# JlinkSwitch.net
KiCad netlist of a schematic drawn in Altium Designer
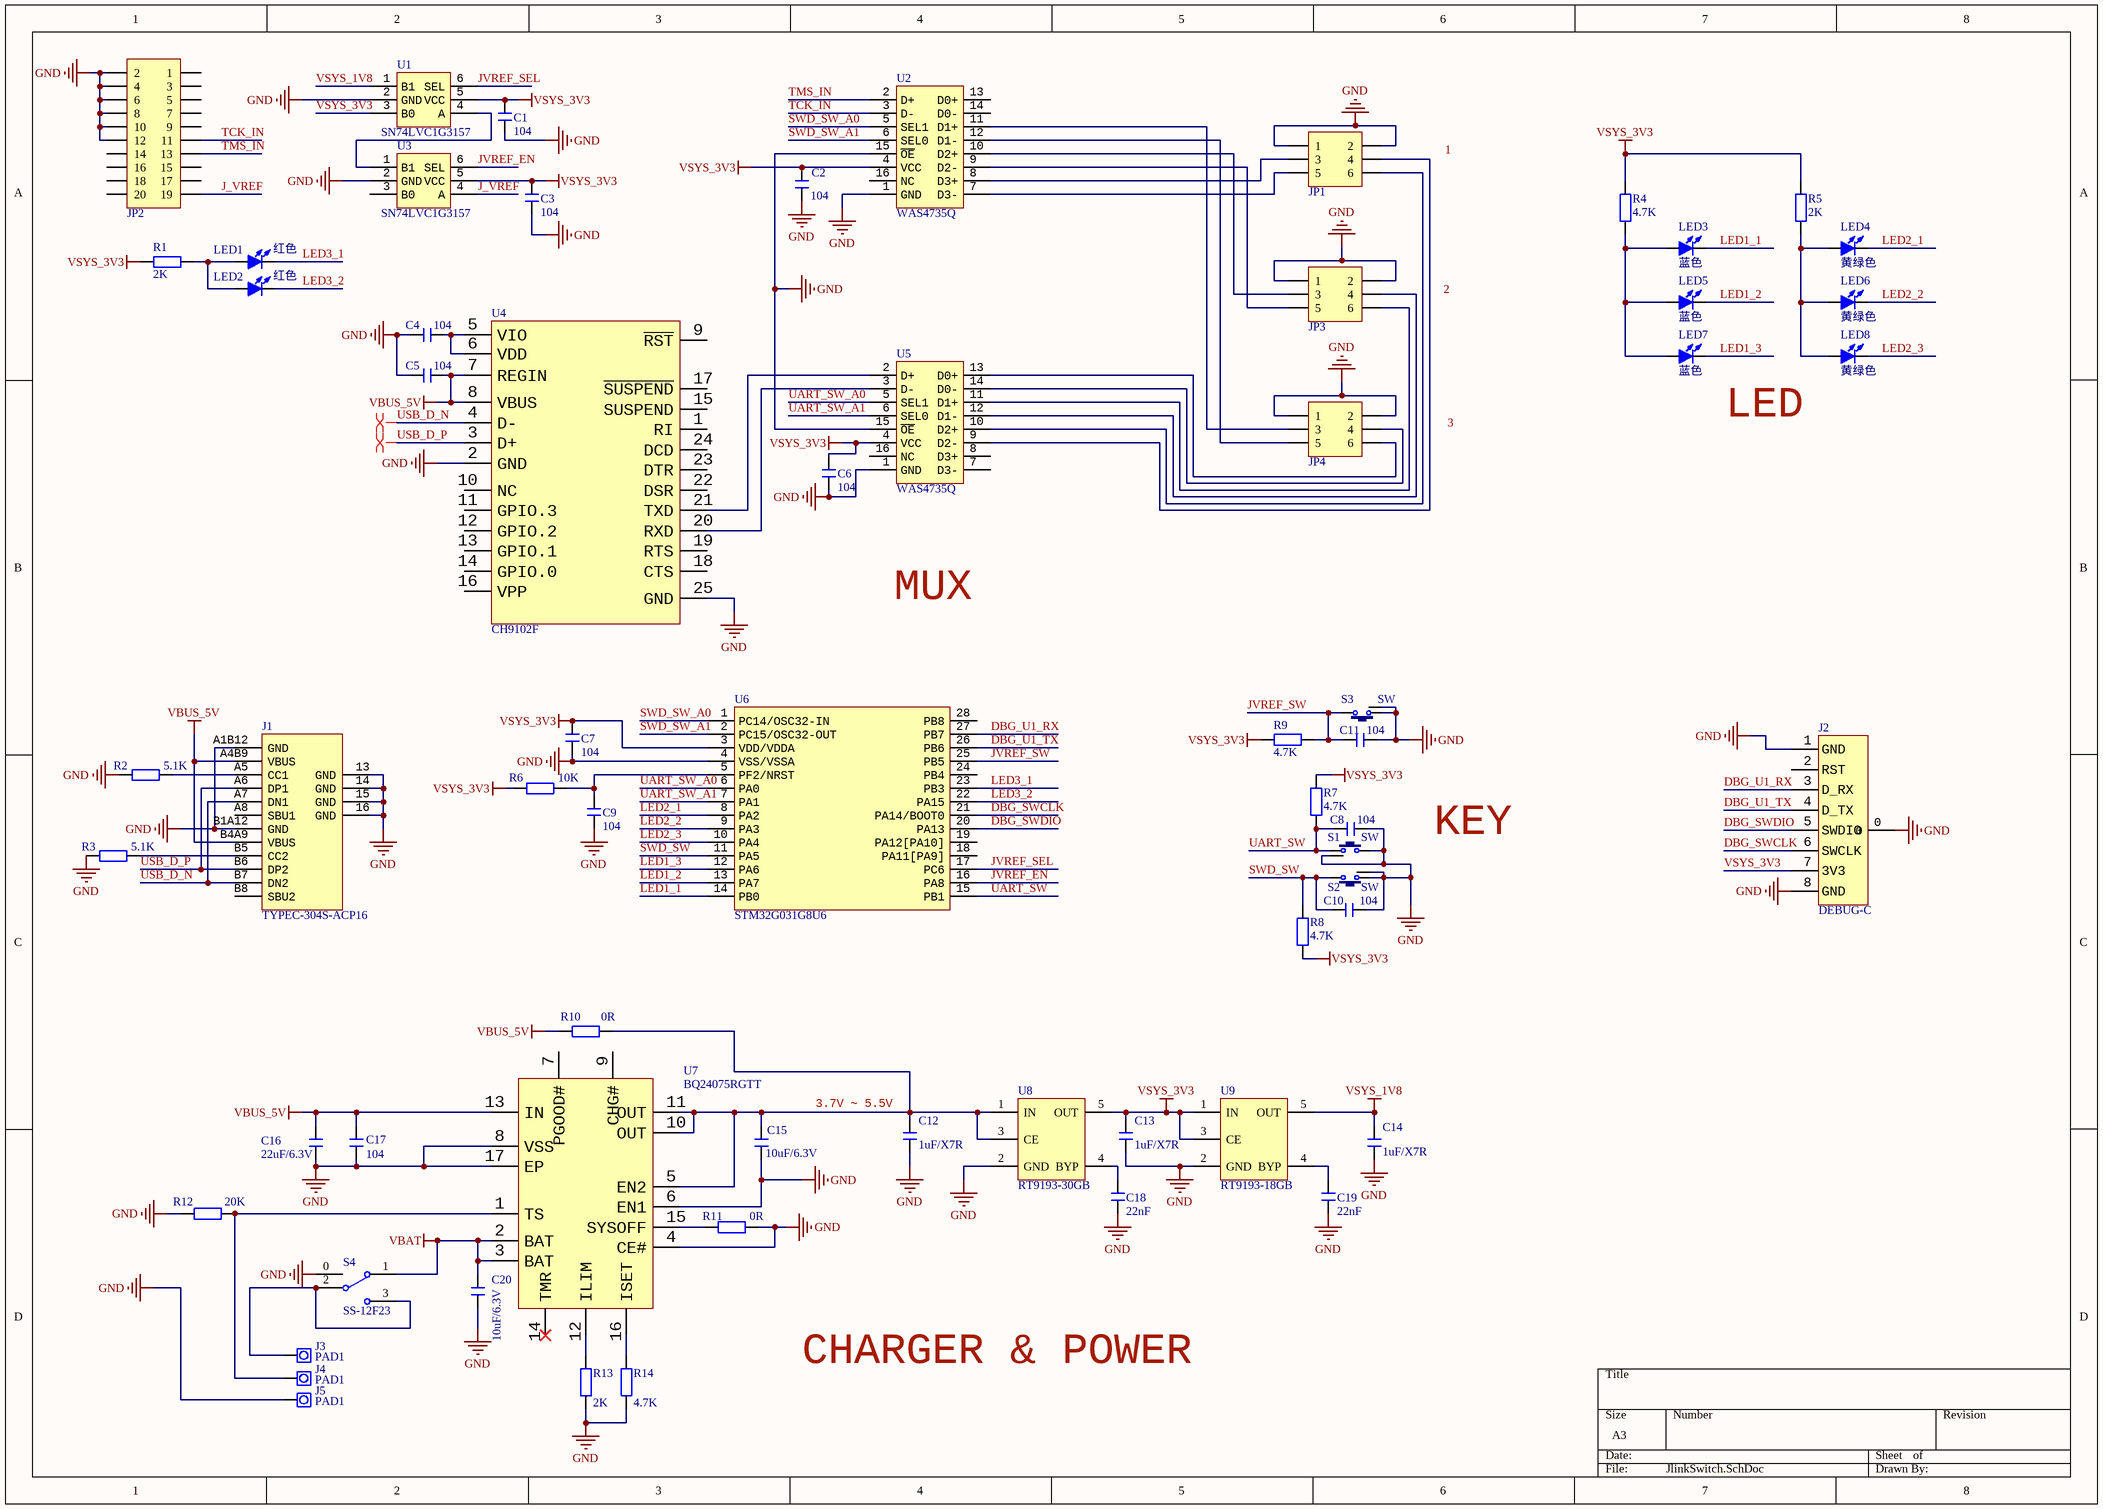
[diagram p0: JlinkSwitch.SchDoc]

(export (version "E")
  (design (tool "Eeschema 10.0.6"))
  (components
    (comp (ref "C1")
      (value "104")
      (footprint "C 0402_L")
      (description "无极性贴片电容")
      (fields (field (name "版权归属") "源创客"))
      (libsource (lib "3.1   - 电阻-电容-电感") (part "C"))
    )
    (comp (ref "C2")
      (value "104")
      (footprint "C 0402_L")
      (description "无极性贴片电容")
      (fields (field (name "版权归属") "源创客"))
      (libsource (lib "3.1   - 电阻-电容-电感") (part "C"))
    )
    (comp (ref "C3")
      (value "104")
      (footprint "C 0402_L")
      (description "无极性贴片电容")
      (fields (field (name "版权归属") "源创客"))
      (libsource (lib "3.1   - 电阻-电容-电感") (part "C"))
    )
    (comp (ref "C4")
      (value "104")
      (footprint "C 0402_L")
      (description "无极性贴片电容")
      (fields (field (name "版权归属") "源创客"))
      (libsource (lib "3.1   - 电阻-电容-电感") (part "C"))
    )
    (comp (ref "C5")
      (value "104")
      (footprint "C 0402_L")
      (description "无极性贴片电容")
      (fields (field (name "版权归属") "源创客"))
      (libsource (lib "3.1   - 电阻-电容-电感") (part "C"))
    )
    (comp (ref "C6")
      (value "104")
      (footprint "C 0402_L")
      (description "无极性贴片电容")
      (fields (field (name "版权归属") "源创客"))
      (libsource (lib "3.1   - 电阻-电容-电感") (part "C"))
    )
    (comp (ref "C7")
      (value "104")
      (footprint "C 0402_L")
      (description "无极性贴片电容")
      (fields (field (name "版权归属") "源创客"))
      (libsource (lib "3.1   - 电阻-电容-电感") (part "C"))
    )
    (comp (ref "C8")
      (value "104")
      (footprint "C 0402_L")
      (description "无极性贴片电容")
      (fields (field (name "版权归属") "源创客"))
      (libsource (lib "3.1   - 电阻-电容-电感") (part "C"))
    )
    (comp (ref "C9")
      (value "104")
      (footprint "C 0402_L")
      (description "无极性贴片电容")
      (fields (field (name "版权归属") "源创客"))
      (libsource (lib "3.1   - 电阻-电容-电感") (part "C"))
    )
    (comp (ref "C10")
      (value "104")
      (footprint "C 0402_L")
      (description "无极性贴片电容")
      (fields (field (name "版权归属") "源创客"))
      (libsource (lib "3.1   - 电阻-电容-电感") (part "C"))
    )
    (comp (ref "C11")
      (value "104")
      (footprint "C 0402_L")
      (description "无极性贴片电容")
      (fields (field (name "版权归属") "源创客"))
      (libsource (lib "3.1   - 电阻-电容-电感") (part "C"))
    )
    (comp (ref "C12")
      (value "1uF/X7R")
      (footprint "C 0402_L")
      (description "无极性贴片电容")
      (fields (field (name "版权归属") "源创客"))
      (libsource (lib "3.1   - 电阻-电容-电感") (part "C"))
    )
    (comp (ref "C13")
      (value "1uF/X7R")
      (footprint "C 0402_L")
      (description "无极性贴片电容")
      (fields (field (name "版权归属") "源创客"))
      (libsource (lib "3.1   - 电阻-电容-电感") (part "C"))
    )
    (comp (ref "C14")
      (value "1uF/X7R")
      (footprint "C 0402_L")
      (description "无极性贴片电容")
      (fields (field (name "版权归属") "源创客"))
      (libsource (lib "3.1   - 电阻-电容-电感") (part "C"))
    )
    (comp (ref "C15")
      (value "10uF/6.3V")
      (footprint "C 0603_L")
      (description "无极性贴片电容")
      (fields (field (name "版权归属") "源创客"))
      (libsource (lib "3.1   - 电阻-电容-电感") (part "C"))
    )
    (comp (ref "C16")
      (value "22uF/6.3V")
      (footprint "C 0603_L")
      (description "无极性贴片电容")
      (fields (field (name "版权归属") "源创客"))
      (libsource (lib "3.1   - 电阻-电容-电感") (part "C"))
    )
    (comp (ref "C17")
      (value "104")
      (footprint "C 0402_L")
      (description "无极性贴片电容")
      (fields (field (name "版权归属") "源创客"))
      (libsource (lib "3.1   - 电阻-电容-电感") (part "C"))
    )
    (comp (ref "C18")
      (value "22nF")
      (footprint "C 0402_L")
      (description "无极性贴片电容")
      (fields (field (name "版权归属") "源创客"))
      (libsource (lib "3.1   - 电阻-电容-电感") (part "C"))
    )
    (comp (ref "C19")
      (value "22nF")
      (footprint "C 0402_L")
      (description "无极性贴片电容")
      (fields (field (name "版权归属") "源创客"))
      (libsource (lib "3.1   - 电阻-电容-电感") (part "C"))
    )
    (comp (ref "C20")
      (value "10uF/6.3V")
      (footprint "C 0603_L")
      (description "无极性贴片电容")
      (fields (field (name "版权归属") "源创客"))
      (libsource (lib "3.1   - 电阻-电容-电感") (part "C"))
    )
    (comp (ref "J1")
      (value "TYPEC-304S-ACP16")
      (footprint "USBC-16P-卧插")
      (description "TYPEC母座16P")
      (libsource (lib "4.1   - 接口类") (part "USB-C/16P"))
    )
    (comp (ref "J2")
      (value "DEBUG-C")
      (footprint "FPC0.5 1H-WS-8P-NARROW")
      (description "带RST的调试接口")
      (libsource (lib "4.1   - 接口类") (part "DEBUG-C"))
    )
    (comp (ref "J3")
      (value "PAD1")
      (footprint "PAD")
      (description "引线焊盘")
      (libsource (lib "15.1 - 未分类器件") (part "PAD1"))
    )
    (comp (ref "J4")
      (value "PAD1")
      (footprint "PAD")
      (description "引线焊盘")
      (libsource (lib "15.1 - 未分类器件") (part "PAD1"))
    )
    (comp (ref "J5")
      (value "PAD1")
      (footprint "PAD")
      (description "引线焊盘")
      (libsource (lib "15.1 - 未分类器件") (part "PAD1"))
    )
    (comp (ref "JP1")
      (value "Header3X2")
      (footprint "HDR2.54-LI-2X3P-侧贴")
      (description "3*2P接插件")
      (fields (field (name "版权归属") "源创客"))
      (libsource (lib "4.5   - 接插件-脚距2.54") (part "Header 3X2"))
    )
    (comp (ref "JP2")
      (value "Header 2X10")
      (footprint "HDR2.54-LI-M-2X10P-侧贴")
      (description "10*2P接插件")
      (fields (field (name "版权归属") "源创客"))
      (libsource (lib "4.5   - 接插件-脚距2.54") (part "Header 10X2"))
    )
    (comp (ref "JP3")
      (value "Header3X2")
      (footprint "HDR2.54-LI-2X3P-侧贴")
      (description "3*2P接插件")
      (fields (field (name "版权归属") "源创客"))
      (libsource (lib "4.5   - 接插件-脚距2.54") (part "Header 3X2"))
    )
    (comp (ref "JP4")
      (value "Header3X2")
      (footprint "HDR2.54-LI-2X3P-侧贴")
      (description "3*2P接插件")
      (fields (field (name "版权归属") "源创客"))
      (libsource (lib "4.5   - 接插件-脚距2.54") (part "Header 3X2"))
    )
    (comp (ref "LED1")
      (value "红色")
      (footprint "LED 0402R")
      (description "贴片LED")
      (fields (field (name "版权归属") "源创客"))
      (libsource (lib "9.1   - LED") (part "LED-SMD"))
    )
    (comp (ref "LED2")
      (value "红色")
      (footprint "LED 0402R")
      (description "贴片LED")
      (fields (field (name "版权归属") "源创客"))
      (libsource (lib "9.1   - LED") (part "LED-SMD"))
    )
    (comp (ref "LED3")
      (value "蓝色")
      (footprint "LED 0402R")
      (description "贴片LED")
      (fields (field (name "版权归属") "源创客"))
      (libsource (lib "9.1   - LED") (part "LED-SMD"))
    )
    (comp (ref "LED4")
      (value "黄绿色")
      (footprint "LED 0402R")
      (description "贴片LED")
      (fields (field (name "版权归属") "源创客"))
      (libsource (lib "9.1   - LED") (part "LED-SMD"))
    )
    (comp (ref "LED5")
      (value "蓝色")
      (footprint "LED 0402R")
      (description "贴片LED")
      (fields (field (name "版权归属") "源创客"))
      (libsource (lib "9.1   - LED") (part "LED-SMD"))
    )
    (comp (ref "LED6")
      (value "黄绿色")
      (footprint "LED 0402R")
      (description "贴片LED")
      (fields (field (name "版权归属") "源创客"))
      (libsource (lib "9.1   - LED") (part "LED-SMD"))
    )
    (comp (ref "LED7")
      (value "蓝色")
      (footprint "LED 0402R")
      (description "贴片LED")
      (fields (field (name "版权归属") "源创客"))
      (libsource (lib "9.1   - LED") (part "LED-SMD"))
    )
    (comp (ref "LED8")
      (value "黄绿色")
      (footprint "LED 0402R")
      (description "贴片LED")
      (fields (field (name "版权归属") "源创客"))
      (libsource (lib "9.1   - LED") (part "LED-SMD"))
    )
    (comp (ref "R1")
      (value "2K")
      (footprint "R 0402_L")
      (description "贴片电阻")
      (fields (field (name "版权归属") "源创客"))
      (libsource (lib "3.1   - 电阻-电容-电感") (part "R"))
    )
    (comp (ref "R2")
      (value "5.1K")
      (footprint "R 0402_L")
      (description "贴片电阻")
      (fields (field (name "版权归属") "源创客"))
      (libsource (lib "3.1   - 电阻-电容-电感") (part "R"))
    )
    (comp (ref "R3")
      (value "5.1K")
      (footprint "R 0402_L")
      (description "贴片电阻")
      (fields (field (name "版权归属") "源创客"))
      (libsource (lib "3.1   - 电阻-电容-电感") (part "R"))
    )
    (comp (ref "R4")
      (value "4.7K")
      (footprint "R 0402_L")
      (description "贴片电阻")
      (fields (field (name "版权归属") "源创客"))
      (libsource (lib "3.1   - 电阻-电容-电感") (part "R"))
    )
    (comp (ref "R5")
      (value "2K")
      (footprint "R 0402_L")
      (description "贴片电阻")
      (fields (field (name "版权归属") "源创客"))
      (libsource (lib "3.1   - 电阻-电容-电感") (part "R"))
    )
    (comp (ref "R6")
      (value "10K")
      (footprint "R 0402_L")
      (description "贴片电阻")
      (fields (field (name "版权归属") "源创客"))
      (libsource (lib "3.1   - 电阻-电容-电感") (part "R"))
    )
    (comp (ref "R7")
      (value "4.7K")
      (footprint "R 0402_L")
      (description "贴片电阻")
      (fields (field (name "版权归属") "源创客"))
      (libsource (lib "3.1   - 电阻-电容-电感") (part "R"))
    )
    (comp (ref "R8")
      (value "4.7K")
      (footprint "R 0402_L")
      (description "贴片电阻")
      (fields (field (name "版权归属") "源创客"))
      (libsource (lib "3.1   - 电阻-电容-电感") (part "R"))
    )
    (comp (ref "R9")
      (value "4.7K")
      (footprint "R 0402_L")
      (description "贴片电阻")
      (fields (field (name "版权归属") "源创客"))
      (libsource (lib "3.1   - 电阻-电容-电感") (part "R"))
    )
    (comp (ref "R10")
      (value "0R")
      (footprint "R 0603_L")
      (description "贴片电阻")
      (fields (field (name "版权归属") "源创客"))
      (libsource (lib "3.1   - 电阻-电容-电感") (part "R"))
    )
    (comp (ref "R11")
      (value "0R")
      (footprint "R 0402_L")
      (description "贴片电阻")
      (fields (field (name "版权归属") "源创客"))
      (libsource (lib "3.1   - 电阻-电容-电感") (part "R"))
    )
    (comp (ref "R12")
      (value "20K")
      (footprint "R 0402_L")
      (description "贴片电阻")
      (fields (field (name "版权归属") "源创客"))
      (libsource (lib "3.1   - 电阻-电容-电感") (part "R"))
    )
    (comp (ref "R13")
      (value "2K")
      (footprint "R 0402_L")
      (description "贴片电阻")
      (fields (field (name "版权归属") "源创客"))
      (libsource (lib "3.1   - 电阻-电容-电感") (part "R"))
    )
    (comp (ref "R14")
      (value "4.7K")
      (footprint "R 0402_L")
      (description "贴片电阻")
      (fields (field (name "版权归属") "源创客"))
      (libsource (lib "3.1   - 电阻-电容-电感") (part "R"))
    )
    (comp (ref "S1")
      (value "SW")
      (footprint "TS 2*4*3.5")
      (description "侧按 按键开关单刀单掷")
      (libsource (lib "") (part "TSW_1"))
    )
    (comp (ref "S2")
      (value "SW")
      (footprint "TS 2*4*3.5")
      (description "侧按 按键开关单刀单掷")
      (libsource (lib "5.1   - 按键-开关") (part "TSW"))
    )
    (comp (ref "S3")
      (value "SW")
      (footprint "TS 2*4*3.5")
      (description "侧按 按键开关单刀单掷")
      (libsource (lib "5.1   - 按键-开关") (part "TSW"))
    )
    (comp (ref "S4")
      (value "SS-12F23")
      (footprint "MSK-12C01-07")
      (description "1路波动开关")
      (fields (field (name "版权归属") "源创客"))
      (libsource (lib "5.1   - 按键-开关") (part "SSW-1P"))
    )
    (comp (ref "U1")
      (value "SN74LVC1G3157")
      (footprint "SC70-6")
      (description "SPDT 7Ω")
      (libsource (lib "1.1   - IC芯片") (part "SN74LVC1G3157DCKR"))
    )
    (comp (ref "U2")
      (value "WAS4735Q")
      (footprint "QFN16-1826")
      (description "模拟开关/多路复用器")
      (libsource (lib "1.1   - IC芯片") (part "WAS4735Q"))
    )
    (comp (ref "U3")
      (value "SN74LVC1G3157")
      (footprint "SC70-6")
      (description "SPDT 7Ω")
      (libsource (lib "1.1   - IC芯片") (part "SN74LVC1G3157DCKR"))
    )
    (comp (ref "U4")
      (value "CH9102F")
      (footprint "QFN24 4x4_L")
      (description "USB转串口芯片")
      (libsource (lib "1.1   - IC芯片") (part "CH9102F"))
    )
    (comp (ref "U5")
      (value "WAS4735Q")
      (footprint "QFN16-1826")
      (description "模拟开关/多路复用器")
      (libsource (lib "1.1   - IC芯片") (part "WAS4735Q"))
    )
    (comp (ref "U6")
      (value "STM32G031G8U6")
      (footprint "UFQFPN-28 4X4")
      (description "M0单片机 QFPN28")
      (libsource (lib "2.1   - STM32系列单片机") (part "STM32G031G8U6"))
    )
    (comp (ref "U7")
      (value "BQ24075RGTT")
      (footprint "VQFN-16-EP(3X3)")
      (description "单节1.5A线性电池充电\r\n电源路径管理 5.5Vout")
      (libsource (lib "1.3   - 电源类芯片") (part "BQ24075RGTx"))
    )
    (comp (ref "U8")
      (value "RT9193-30GB")
      (footprint "SOT23-5")
      (description "低功耗LDO Id=35uA")
      (libsource (lib "1.3   - 电源类芯片") (part "XC6210B332MR"))
    )
    (comp (ref "U9")
      (value "RT9193-18GB")
      (footprint "SOT23-5")
      (description "低功耗LDO Id=35uA")
      (libsource (lib "1.3   - 电源类芯片") (part "XC6210B332MR"))
    )
  )
  (nets
    (net (code "1") (name "/DBG_SWCLK") (class "Default")
      (node (ref "J2") (pin "6") (pinfunction "SWCLK_6") (pintype "passive"))
      (node (ref "U6") (pin "21") (pinfunction "PA14/BOOT0_21") (pintype "passive"))
    )
    (net (code "2") (name "/DBG_SWDIO") (class "Default")
      (node (ref "J2") (pin "5") (pinfunction "SWDIO_5") (pintype "passive"))
      (node (ref "U6") (pin "20") (pinfunction "PA13_20") (pintype "passive"))
    )
    (net (code "3") (name "/DBG_U1_RX") (class "Default")
      (node (ref "J2") (pin "3") (pinfunction "D_RX_3") (pintype "passive"))
      (node (ref "U6") (pin "27") (pinfunction "PB7_27") (pintype "passive"))
    )
    (net (code "4") (name "/DBG_U1_TX") (class "Default")
      (node (ref "J2") (pin "4") (pinfunction "D_TX_4") (pintype "passive"))
      (node (ref "U6") (pin "26") (pinfunction "PB6_26") (pintype "passive"))
    )
    (net (code "5") (name "/JVREF_EN") (class "Default")
      (node (ref "U3") (pin "6") (pinfunction "SEL_6") (pintype "passive"))
      (node (ref "U6") (pin "16") (pinfunction "PA8_16") (pintype "passive"))
    )
    (net (code "6") (name "/JVREF_SEL") (class "Default")
      (node (ref "U1") (pin "6") (pinfunction "SEL_6") (pintype "passive"))
      (node (ref "U6") (pin "17") (pinfunction "PC6_17") (pintype "passive"))
    )
    (net (code "7") (name "/JVREF_SW") (class "Default")
      (node (ref "C11") (pin "1") (pinfunction "1_1") (pintype "passive"))
      (node (ref "R9") (pin "1") (pinfunction "1_1") (pintype "passive"))
      (node (ref "S3") (pin "2") (pinfunction "2_2") (pintype "passive"))
      (node (ref "U6") (pin "25") (pinfunction "PB5_25") (pintype "passive"))
    )
    (net (code "8") (name "/J_VREF") (class "Default")
      (node (ref "JP2") (pin "19") (pinfunction "19_19") (pintype "passive"))
      (node (ref "U3") (pin "4") (pinfunction "A_4") (pintype "passive"))
    )
    (net (code "9") (name "/LED1_1") (class "Default")
      (node (ref "LED3") (pin "1") (pinfunction "K_1") (pintype "passive"))
      (node (ref "U6") (pin "14") (pinfunction "PB0_14") (pintype "passive"))
    )
    (net (code "10") (name "/LED1_2") (class "Default")
      (node (ref "LED5") (pin "1") (pinfunction "K_1") (pintype "passive"))
      (node (ref "U6") (pin "13") (pinfunction "PA7_13") (pintype "passive"))
    )
    (net (code "11") (name "/LED1_3") (class "Default")
      (node (ref "LED7") (pin "1") (pinfunction "K_1") (pintype "passive"))
      (node (ref "U6") (pin "12") (pinfunction "PA6_12") (pintype "passive"))
    )
    (net (code "12") (name "/LED2_1") (class "Default")
      (node (ref "LED4") (pin "1") (pinfunction "K_1") (pintype "passive"))
      (node (ref "U6") (pin "8") (pinfunction "PA2_8") (pintype "passive"))
    )
    (net (code "13") (name "/LED2_2") (class "Default")
      (node (ref "LED6") (pin "1") (pinfunction "K_1") (pintype "passive"))
      (node (ref "U6") (pin "9") (pinfunction "PA3_9") (pintype "passive"))
    )
    (net (code "14") (name "/LED2_3") (class "Default")
      (node (ref "LED8") (pin "1") (pinfunction "K_1") (pintype "passive"))
      (node (ref "U6") (pin "10") (pinfunction "PA4_10") (pintype "passive"))
    )
    (net (code "15") (name "/LED3_1") (class "Default")
      (node (ref "LED1") (pin "1") (pinfunction "K_1") (pintype "passive"))
      (node (ref "U6") (pin "23") (pinfunction "PB3_23") (pintype "passive"))
    )
    (net (code "16") (name "/LED3_2") (class "Default")
      (node (ref "LED2") (pin "1") (pinfunction "K_1") (pintype "passive"))
      (node (ref "U6") (pin "22") (pinfunction "PA15_22") (pintype "passive"))
    )
    (net (code "17") (name "/SWD_SW") (class "Default")
      (node (ref "C10") (pin "1") (pinfunction "1_1") (pintype "passive"))
      (node (ref "R8") (pin "2") (pinfunction "2_2") (pintype "passive"))
      (node (ref "S2") (pin "2") (pinfunction "2_2") (pintype "passive"))
      (node (ref "U6") (pin "11") (pinfunction "PA5_11") (pintype "passive"))
    )
    (net (code "18") (name "/SWD_SW_A0") (class "Default")
      (node (ref "U2") (pin "5") (pinfunction "SEL1_5") (pintype "passive"))
      (node (ref "U6") (pin "1") (pinfunction "PC14/OSC32-IN_1") (pintype "passive"))
    )
    (net (code "19") (name "/SWD_SW_A1") (class "Default")
      (node (ref "U2") (pin "6") (pinfunction "SEL0_6") (pintype "passive"))
      (node (ref "U6") (pin "2") (pinfunction "PC15/OSC32-OUT_2") (pintype "passive"))
    )
    (net (code "20") (name "/TCK_IN") (class "Default")
      (node (ref "JP2") (pin "11") (pinfunction "11_11") (pintype "passive"))
      (node (ref "U2") (pin "3") (pinfunction "D-_3") (pintype "passive"))
    )
    (net (code "21") (name "/TMS_IN") (class "Default")
      (node (ref "JP2") (pin "13") (pinfunction "13_13") (pintype "passive"))
      (node (ref "U2") (pin "2") (pinfunction "D+_2") (pintype "passive"))
    )
    (net (code "22") (name "/UART_SW") (class "Default")
      (node (ref "C8") (pin "1") (pinfunction "1_1") (pintype "passive"))
      (node (ref "R7") (pin "1") (pinfunction "1_1") (pintype "passive"))
      (node (ref "S1") (pin "1") (pinfunction "1_1") (pintype "passive"))
      (node (ref "U6") (pin "15") (pinfunction "PB1_15") (pintype "passive"))
    )
    (net (code "23") (name "/UART_SW_A0") (class "Default")
      (node (ref "U5") (pin "5") (pinfunction "SEL1_5") (pintype "passive"))
      (node (ref "U6") (pin "6") (pinfunction "PA0_6") (pintype "passive"))
    )
    (net (code "24") (name "/UART_SW_A1") (class "Default")
      (node (ref "U5") (pin "6") (pinfunction "SEL0_6") (pintype "passive"))
      (node (ref "U6") (pin "7") (pinfunction "PA1_7") (pintype "passive"))
    )
    (net (code "25") (name "/USB_D_N") (class "Default")
      (node (ref "J1") (pin "A7") (pinfunction "DN1_A7") (pintype "passive"))
      (node (ref "J1") (pin "B7") (pinfunction "DN2_B7") (pintype "passive"))
      (node (ref "U4") (pin "4") (pinfunction "D-_4") (pintype "passive"))
    )
    (net (code "26") (name "/USB_D_P") (class "Default")
      (node (ref "J1") (pin "A6") (pinfunction "DP1_A6") (pintype "passive"))
      (node (ref "J1") (pin "B6") (pinfunction "DP2_B6") (pintype "passive"))
      (node (ref "U4") (pin "3") (pinfunction "D+_3") (pintype "passive"))
    )
    (net (code "27") (name "GND") (class "Default")
      (node (ref "C1") (pin "2") (pinfunction "2_2") (pintype "passive"))
      (node (ref "C10") (pin "2") (pinfunction "2_2") (pintype "passive"))
      (node (ref "C11") (pin "2") (pinfunction "2_2") (pintype "passive"))
      (node (ref "C12") (pin "1") (pinfunction "1_1") (pintype "passive"))
      (node (ref "C13") (pin "1") (pinfunction "1_1") (pintype "passive"))
      (node (ref "C14") (pin "1") (pinfunction "1_1") (pintype "passive"))
      (node (ref "C15") (pin "1") (pinfunction "1_1") (pintype "passive"))
      (node (ref "C16") (pin "1") (pinfunction "1_1") (pintype "passive"))
      (node (ref "C17") (pin "1") (pinfunction "1_1") (pintype "passive"))
      (node (ref "C18") (pin "1") (pinfunction "1_1") (pintype "passive"))
      (node (ref "C19") (pin "1") (pinfunction "1_1") (pintype "passive"))
      (node (ref "C2") (pin "1") (pinfunction "1_1") (pintype "passive"))
      (node (ref "C20") (pin "1") (pinfunction "1_1") (pintype "passive"))
      (node (ref "C3") (pin "2") (pinfunction "2_2") (pintype "passive"))
      (node (ref "C4") (pin "2") (pinfunction "2_2") (pintype "passive"))
      (node (ref "C5") (pin "2") (pinfunction "2_2") (pintype "passive"))
      (node (ref "C6") (pin "1") (pinfunction "1_1") (pintype "passive"))
      (node (ref "C7") (pin "2") (pinfunction "2_2") (pintype "passive"))
      (node (ref "C8") (pin "2") (pinfunction "2_2") (pintype "passive"))
      (node (ref "C9") (pin "2") (pinfunction "2_2") (pintype "passive"))
      (node (ref "J1") (pin "13") (pinfunction "GND_13") (pintype "passive"))
      (node (ref "J1") (pin "14") (pinfunction "GND_14") (pintype "passive"))
      (node (ref "J1") (pin "15") (pinfunction "GND_15") (pintype "passive"))
      (node (ref "J1") (pin "16") (pinfunction "GND_16") (pintype "passive"))
      (node (ref "J1") (pin "A1B12") (pinfunction "GND_A1B12") (pintype "passive"))
      (node (ref "J1") (pin "B1A12") (pinfunction "GND_B1A12") (pintype "passive"))
      (node (ref "J2") (pin "0") (pinfunction "0_0") (pintype "passive"))
      (node (ref "J2") (pin "1") (pinfunction "GND_1") (pintype "passive"))
      (node (ref "J2") (pin "8") (pinfunction "GND_8") (pintype "passive"))
      (node (ref "J5") (pin "1") (pinfunction "1_1") (pintype "passive"))
      (node (ref "JP1") (pin "1") (pinfunction "1_1") (pintype "passive"))
      (node (ref "JP1") (pin "2") (pinfunction "2_2") (pintype "passive"))
      (node (ref "JP2") (pin "10") (pinfunction "10_10") (pintype "passive"))
      (node (ref "JP2") (pin "12") (pinfunction "12_12") (pintype "passive"))
      (node (ref "JP2") (pin "2") (pinfunction "2_2") (pintype "passive"))
      (node (ref "JP2") (pin "4") (pinfunction "4_4") (pintype "passive"))
      (node (ref "JP2") (pin "6") (pinfunction "6_6") (pintype "passive"))
      (node (ref "JP2") (pin "8") (pinfunction "8_8") (pintype "passive"))
      (node (ref "JP3") (pin "1") (pinfunction "1_1") (pintype "passive"))
      (node (ref "JP3") (pin "2") (pinfunction "2_2") (pintype "passive"))
      (node (ref "JP4") (pin "1") (pinfunction "1_1") (pintype "passive"))
      (node (ref "JP4") (pin "2") (pinfunction "2_2") (pintype "passive"))
      (node (ref "R11") (pin "1") (pinfunction "1_1") (pintype "passive"))
      (node (ref "R12") (pin "1") (pinfunction "1_1") (pintype "passive"))
      (node (ref "R13") (pin "1") (pinfunction "1_1") (pintype "passive"))
      (node (ref "R14") (pin "1") (pinfunction "1_1") (pintype "passive"))
      (node (ref "R2") (pin "1") (pinfunction "1_1") (pintype "passive"))
      (node (ref "R3") (pin "1") (pinfunction "1_1") (pintype "passive"))
      (node (ref "S1") (pin "0") (pinfunction "0_0") (pintype "passive"))
      (node (ref "S1") (pin "2") (pinfunction "2_2") (pintype "passive"))
      (node (ref "S2") (pin "0") (pinfunction "0_0") (pintype "passive"))
      (node (ref "S2") (pin "1") (pinfunction "1_1") (pintype "passive"))
      (node (ref "S3") (pin "0") (pinfunction "0_0") (pintype "passive"))
      (node (ref "S3") (pin "1") (pinfunction "1_1") (pintype "passive"))
      (node (ref "S4") (pin "0") (pinfunction "0_0") (pintype "passive"))
      (node (ref "U1") (pin "2") (pinfunction "GND_2") (pintype "passive"))
      (node (ref "U2") (pin "1") (pinfunction "GND_1") (pintype "passive"))
      (node (ref "U2") (pin "15") (pinfunction "~{OE}_15") (pintype "passive"))
      (node (ref "U3") (pin "2") (pinfunction "GND_2") (pintype "passive"))
      (node (ref "U4") (pin "2") (pinfunction "GND_2") (pintype "passive"))
      (node (ref "U4") (pin "25") (pinfunction "GND_25") (pintype "passive"))
      (node (ref "U5") (pin "1") (pinfunction "GND_1") (pintype "passive"))
      (node (ref "U5") (pin "15") (pinfunction "~{OE}_15") (pintype "passive"))
      (node (ref "U6") (pin "4") (pinfunction "VSS/VSSA_4") (pintype "passive"))
      (node (ref "U7") (pin "17") (pinfunction "EP_17") (pintype "passive"))
      (node (ref "U7") (pin "4") (pinfunction "CE#_4") (pintype "passive"))
      (node (ref "U7") (pin "6") (pinfunction "EN1_6") (pintype "passive"))
      (node (ref "U7") (pin "8") (pinfunction "VSS_8") (pintype "passive"))
      (node (ref "U8") (pin "2") (pinfunction "GND_2") (pintype "passive"))
      (node (ref "U9") (pin "2") (pinfunction "GND_2") (pintype "passive"))
    )
    (net (code "28") (name "Net-(J1-CC1)") (class "Default")
      (node (ref "J1") (pin "A5") (pinfunction "CC1_A5") (pintype "passive"))
      (node (ref "R2") (pin "2") (pinfunction "2_2") (pintype "passive"))
    )
    (net (code "29") (name "Net-(J1-CC2)") (class "Default")
      (node (ref "J1") (pin "B5") (pinfunction "CC2_B5") (pintype "passive"))
      (node (ref "R3") (pin "2") (pinfunction "2_2") (pintype "passive"))
    )
    (net (code "30") (name "Net-(J3-Pad1)") (class "Default")
      (node (ref "J3") (pin "1") (pinfunction "1_1") (pintype "passive"))
      (node (ref "S4") (pin "2") (pinfunction "2_2") (pintype "passive"))
      (node (ref "S4") (pin "3") (pinfunction "3_3") (pintype "passive"))
    )
    (net (code "31") (name "Net-(LED1-A)") (class "Default")
      (node (ref "LED1") (pin "2") (pinfunction "A_2") (pintype "passive"))
      (node (ref "LED2") (pin "2") (pinfunction "A_2") (pintype "passive"))
      (node (ref "R1") (pin "1") (pinfunction "1_1") (pintype "passive"))
    )
    (net (code "32") (name "Net-(LED3-A)") (class "Default")
      (node (ref "LED3") (pin "2") (pinfunction "A_2") (pintype "passive"))
      (node (ref "LED5") (pin "2") (pinfunction "A_2") (pintype "passive"))
      (node (ref "LED7") (pin "2") (pinfunction "A_2") (pintype "passive"))
      (node (ref "R4") (pin "1") (pinfunction "1_1") (pintype "passive"))
    )
    (net (code "33") (name "Net-(LED4-A)") (class "Default")
      (node (ref "LED4") (pin "2") (pinfunction "A_2") (pintype "passive"))
      (node (ref "LED6") (pin "2") (pinfunction "A_2") (pintype "passive"))
      (node (ref "LED8") (pin "2") (pinfunction "A_2") (pintype "passive"))
      (node (ref "R5") (pin "1") (pinfunction "1_1") (pintype "passive"))
    )
    (net (code "34") (name "Net-(U1-A)") (class "Default")
      (node (ref "U1") (pin "4") (pinfunction "A_4") (pintype "passive"))
      (node (ref "U3") (pin "1") (pinfunction "B1_1") (pintype "passive"))
    )
    (net (code "35") (name "Net-(U2-D1+)") (class "Default")
      (node (ref "JP4") (pin "3") (pinfunction "3_3") (pintype "passive"))
      (node (ref "U2") (pin "11") (pinfunction "D1+_11") (pintype "passive"))
    )
    (net (code "36") (name "Net-(U2-D1-)") (class "Default")
      (node (ref "JP4") (pin "5") (pinfunction "5_5") (pintype "passive"))
      (node (ref "U2") (pin "12") (pinfunction "D1-_12") (pintype "passive"))
    )
    (net (code "37") (name "Net-(U2-D2+)") (class "Default")
      (node (ref "JP3") (pin "3") (pinfunction "3_3") (pintype "passive"))
      (node (ref "U2") (pin "10") (pinfunction "D2+_10") (pintype "passive"))
    )
    (net (code "38") (name "Net-(U2-D2-)") (class "Default")
      (node (ref "JP3") (pin "5") (pinfunction "5_5") (pintype "passive"))
      (node (ref "U2") (pin "9") (pinfunction "D2-_9") (pintype "passive"))
    )
    (net (code "39") (name "Net-(U2-D3+)") (class "Default")
      (node (ref "JP1") (pin "3") (pinfunction "3_3") (pintype "passive"))
      (node (ref "U2") (pin "8") (pinfunction "D3+_8") (pintype "passive"))
    )
    (net (code "40") (name "Net-(U2-D3-)") (class "Default")
      (node (ref "JP1") (pin "5") (pinfunction "5_5") (pintype "passive"))
      (node (ref "U2") (pin "7") (pinfunction "D3-_7") (pintype "passive"))
    )
    (net (code "41") (name "Net-(U4-RXD)") (class "Default")
      (node (ref "U4") (pin "20") (pinfunction "RXD_20") (pintype "passive"))
      (node (ref "U5") (pin "3") (pinfunction "D-_3") (pintype "passive"))
    )
    (net (code "42") (name "Net-(U4-TXD)") (class "Default")
      (node (ref "U4") (pin "21") (pinfunction "TXD_21") (pintype "passive"))
      (node (ref "U5") (pin "2") (pinfunction "D+_2") (pintype "passive"))
    )
    (net (code "43") (name "Net-(U4-VDD)") (class "Default")
      (node (ref "C4") (pin "1") (pinfunction "1_1") (pintype "passive"))
      (node (ref "U4") (pin "5") (pinfunction "VIO_5") (pintype "passive"))
      (node (ref "U4") (pin "6") (pinfunction "VDD_6") (pintype "passive"))
    )
    (net (code "44") (name "Net-(U5-D0+)") (class "Default")
      (node (ref "JP4") (pin "6") (pinfunction "6_6") (pintype "passive"))
      (node (ref "U5") (pin "13") (pinfunction "D0+_13") (pintype "passive"))
    )
    (net (code "45") (name "Net-(U5-D0-)") (class "Default")
      (node (ref "JP4") (pin "4") (pinfunction "4_4") (pintype "passive"))
      (node (ref "U5") (pin "14") (pinfunction "D0-_14") (pintype "passive"))
    )
    (net (code "46") (name "Net-(U5-D1+)") (class "Default")
      (node (ref "JP3") (pin "6") (pinfunction "6_6") (pintype "passive"))
      (node (ref "U5") (pin "11") (pinfunction "D1+_11") (pintype "passive"))
    )
    (net (code "47") (name "Net-(U5-D1-)") (class "Default")
      (node (ref "JP3") (pin "4") (pinfunction "4_4") (pintype "passive"))
      (node (ref "U5") (pin "12") (pinfunction "D1-_12") (pintype "passive"))
    )
    (net (code "48") (name "Net-(U5-D2+)") (class "Default")
      (node (ref "JP1") (pin "6") (pinfunction "6_6") (pintype "passive"))
      (node (ref "U5") (pin "10") (pinfunction "D2+_10") (pintype "passive"))
    )
    (net (code "49") (name "Net-(U5-D2-)") (class "Default")
      (node (ref "JP1") (pin "4") (pinfunction "4_4") (pintype "passive"))
      (node (ref "U5") (pin "9") (pinfunction "D2-_9") (pintype "passive"))
    )
    (net (code "50") (name "Net-(U6-PF2{slash}NRST)") (class "Default")
      (node (ref "C9") (pin "1") (pinfunction "1_1") (pintype "passive"))
      (node (ref "R6") (pin "2") (pinfunction "2_2") (pintype "passive"))
      (node (ref "U6") (pin "5") (pinfunction "PF2/NRST_5") (pintype "passive"))
    )
    (net (code "51") (name "Net-(U7-EN2)") (class "Default")
      (node (ref "C12") (pin "2") (pinfunction "2_2") (pintype "passive"))
      (node (ref "C15") (pin "2") (pinfunction "2_2") (pintype "passive"))
      (node (ref "R10") (pin "2") (pinfunction "2_2") (pintype "passive"))
      (node (ref "U7") (pin "10") (pinfunction "OUT_10") (pintype "passive"))
      (node (ref "U7") (pin "11") (pinfunction "OUT_11") (pintype "passive"))
      (node (ref "U7") (pin "5") (pinfunction "EN2_5") (pintype "passive"))
      (node (ref "U8") (pin "1") (pinfunction "IN_1") (pintype "passive"))
      (node (ref "U8") (pin "3") (pinfunction "CE_3") (pintype "passive"))
    )
    (net (code "52") (name "Net-(U7-ILIM)") (class "Default")
      (node (ref "R13") (pin "2") (pinfunction "2_2") (pintype "passive"))
      (node (ref "U7") (pin "12") (pinfunction "ILIM_12") (pintype "passive"))
    )
    (net (code "53") (name "Net-(U7-ISET)") (class "Default")
      (node (ref "R14") (pin "2") (pinfunction "2_2") (pintype "passive"))
      (node (ref "U7") (pin "16") (pinfunction "ISET_16") (pintype "passive"))
    )
    (net (code "54") (name "Net-(U7-SYSOFF)") (class "Default")
      (node (ref "R11") (pin "2") (pinfunction "2_2") (pintype "passive"))
      (node (ref "U7") (pin "15") (pinfunction "SYSOFF_15") (pintype "passive"))
    )
    (net (code "55") (name "Net-(U7-TS)") (class "Default")
      (node (ref "J4") (pin "1") (pinfunction "1_1") (pintype "passive"))
      (node (ref "R12") (pin "2") (pinfunction "2_2") (pintype "passive"))
      (node (ref "U7") (pin "1") (pinfunction "TS_1") (pintype "passive"))
    )
    (net (code "56") (name "Net-(U8-BYP)") (class "Default")
      (node (ref "C18") (pin "2") (pinfunction "2_2") (pintype "passive"))
      (node (ref "U8") (pin "4") (pinfunction "BYP_4") (pintype "passive"))
    )
    (net (code "57") (name "Net-(U9-BYP)") (class "Default")
      (node (ref "C19") (pin "2") (pinfunction "2_2") (pintype "passive"))
      (node (ref "U9") (pin "4") (pinfunction "BYP_4") (pintype "passive"))
    )
    (net (code "58") (name "VBAT") (class "Default")
      (node (ref "C20") (pin "2") (pinfunction "2_2") (pintype "passive"))
      (node (ref "S4") (pin "1") (pinfunction "1_1") (pintype "passive"))
      (node (ref "U7") (pin "2") (pinfunction "BAT_2") (pintype "passive"))
      (node (ref "U7") (pin "3") (pinfunction "BAT_3") (pintype "passive"))
    )
    (net (code "59") (name "VBUS_5V") (class "Default")
      (node (ref "C16") (pin "2") (pinfunction "2_2") (pintype "passive"))
      (node (ref "C17") (pin "2") (pinfunction "2_2") (pintype "passive"))
      (node (ref "C5") (pin "1") (pinfunction "1_1") (pintype "passive"))
      (node (ref "J1") (pin "A4B9") (pinfunction "VBUS_A4B9") (pintype "passive"))
      (node (ref "J1") (pin "B4A9") (pinfunction "VBUS_B4A9") (pintype "passive"))
      (node (ref "R10") (pin "1") (pinfunction "1_1") (pintype "passive"))
      (node (ref "U4") (pin "7") (pinfunction "REGIN_7") (pintype "passive"))
      (node (ref "U4") (pin "8") (pinfunction "VBUS_8") (pintype "passive"))
      (node (ref "U7") (pin "13") (pinfunction "IN_13") (pintype "passive"))
    )
    (net (code "60") (name "VSYS_1V8") (class "Default")
      (node (ref "C14") (pin "2") (pinfunction "2_2") (pintype "passive"))
      (node (ref "U1") (pin "1") (pinfunction "B1_1") (pintype "passive"))
      (node (ref "U9") (pin "5") (pinfunction "OUT_5") (pintype "passive"))
    )
    (net (code "61") (name "VSYS_3V3") (class "Default")
      (node (ref "C1") (pin "1") (pinfunction "1_1") (pintype "passive"))
      (node (ref "C13") (pin "2") (pinfunction "2_2") (pintype "passive"))
      (node (ref "C2") (pin "2") (pinfunction "2_2") (pintype "passive"))
      (node (ref "C3") (pin "1") (pinfunction "1_1") (pintype "passive"))
      (node (ref "C6") (pin "2") (pinfunction "2_2") (pintype "passive"))
      (node (ref "C7") (pin "1") (pinfunction "1_1") (pintype "passive"))
      (node (ref "J2") (pin "7") (pinfunction "3V3_7") (pintype "passive"))
      (node (ref "R1") (pin "2") (pinfunction "2_2") (pintype "passive"))
      (node (ref "R4") (pin "2") (pinfunction "2_2") (pintype "passive"))
      (node (ref "R5") (pin "2") (pinfunction "2_2") (pintype "passive"))
      (node (ref "R6") (pin "1") (pinfunction "1_1") (pintype "passive"))
      (node (ref "R7") (pin "2") (pinfunction "2_2") (pintype "passive"))
      (node (ref "R8") (pin "1") (pinfunction "1_1") (pintype "passive"))
      (node (ref "R9") (pin "2") (pinfunction "2_2") (pintype "passive"))
      (node (ref "U1") (pin "3") (pinfunction "B0_3") (pintype "passive"))
      (node (ref "U1") (pin "5") (pinfunction "VCC_5") (pintype "passive"))
      (node (ref "U2") (pin "4") (pinfunction "VCC_4") (pintype "passive"))
      (node (ref "U3") (pin "5") (pinfunction "VCC_5") (pintype "passive"))
      (node (ref "U5") (pin "4") (pinfunction "VCC_4") (pintype "passive"))
      (node (ref "U6") (pin "3") (pinfunction "VDD/VDDA_3") (pintype "passive"))
      (node (ref "U8") (pin "5") (pinfunction "OUT_5") (pintype "passive"))
      (node (ref "U9") (pin "1") (pinfunction "IN_1") (pintype "passive"))
      (node (ref "U9") (pin "3") (pinfunction "CE_3") (pintype "passive"))
    )
    (net (code "62") (name "unconnected-(J1-SBU1-PadA8)") (class "Default")
      (node (ref "J1") (pin "A8") (pinfunction "SBU1_A8") (pintype "passive"))
    )
    (net (code "63") (name "unconnected-(J1-SBU2-PadB8)") (class "Default")
      (node (ref "J1") (pin "B8") (pinfunction "SBU2_B8") (pintype "passive"))
    )
    (net (code "64") (name "unconnected-(J2-RST-Pad2)") (class "Default")
      (node (ref "J2") (pin "2") (pinfunction "RST_2") (pintype "passive"))
    )
    (net (code "65") (name "unconnected-(JP2-Pad1)") (class "Default")
      (node (ref "JP2") (pin "1") (pinfunction "1_1") (pintype "passive"))
    )
    (net (code "66") (name "unconnected-(JP2-Pad3)") (class "Default")
      (node (ref "JP2") (pin "3") (pinfunction "3_3") (pintype "passive"))
    )
    (net (code "67") (name "unconnected-(JP2-Pad5)") (class "Default")
      (node (ref "JP2") (pin "5") (pinfunction "5_5") (pintype "passive"))
    )
    (net (code "68") (name "unconnected-(JP2-Pad7)") (class "Default")
      (node (ref "JP2") (pin "7") (pinfunction "7_7") (pintype "passive"))
    )
    (net (code "69") (name "unconnected-(JP2-Pad9)") (class "Default")
      (node (ref "JP2") (pin "9") (pinfunction "9_9") (pintype "passive"))
    )
    (net (code "70") (name "unconnected-(JP2-Pad14)") (class "Default")
      (node (ref "JP2") (pin "14") (pinfunction "14_14") (pintype "passive"))
    )
    (net (code "71") (name "unconnected-(JP2-Pad15)") (class "Default")
      (node (ref "JP2") (pin "15") (pinfunction "15_15") (pintype "passive"))
    )
    (net (code "72") (name "unconnected-(JP2-Pad16)") (class "Default")
      (node (ref "JP2") (pin "16") (pinfunction "16_16") (pintype "passive"))
    )
    (net (code "73") (name "unconnected-(JP2-Pad17)") (class "Default")
      (node (ref "JP2") (pin "17") (pinfunction "17_17") (pintype "passive"))
    )
    (net (code "74") (name "unconnected-(JP2-Pad18)") (class "Default")
      (node (ref "JP2") (pin "18") (pinfunction "18_18") (pintype "passive"))
    )
    (net (code "75") (name "unconnected-(JP2-Pad20)") (class "Default")
      (node (ref "JP2") (pin "20") (pinfunction "20_20") (pintype "passive"))
    )
    (net (code "76") (name "unconnected-(U2-D0+-Pad13)") (class "Default")
      (node (ref "U2") (pin "13") (pinfunction "D0+_13") (pintype "passive"))
    )
    (net (code "77") (name "unconnected-(U2-D0--Pad14)") (class "Default")
      (node (ref "U2") (pin "14") (pinfunction "D0-_14") (pintype "passive"))
    )
    (net (code "78") (name "unconnected-(U2-NC-Pad16)") (class "Default")
      (node (ref "U2") (pin "16") (pinfunction "NC_16") (pintype "passive"))
    )
    (net (code "79") (name "unconnected-(U3-B0-Pad3)") (class "Default")
      (node (ref "U3") (pin "3") (pinfunction "B0_3") (pintype "passive"))
    )
    (net (code "80") (name "unconnected-(U4-CTS-Pad18)") (class "Default")
      (node (ref "U4") (pin "18") (pinfunction "CTS_18") (pintype "passive"))
    )
    (net (code "81") (name "unconnected-(U4-DCD-Pad24)") (class "Default")
      (node (ref "U4") (pin "24") (pinfunction "DCD_24") (pintype "passive"))
    )
    (net (code "82") (name "unconnected-(U4-DSR-Pad22)") (class "Default")
      (node (ref "U4") (pin "22") (pinfunction "DSR_22") (pintype "passive"))
    )
    (net (code "83") (name "unconnected-(U4-DTR-Pad23)") (class "Default")
      (node (ref "U4") (pin "23") (pinfunction "DTR_23") (pintype "passive"))
    )
    (net (code "84") (name "unconnected-(U4-GPIO.0-Pad14)") (class "Default")
      (node (ref "U4") (pin "14") (pinfunction "GPIO.0_14") (pintype "passive"))
    )
    (net (code "85") (name "unconnected-(U4-GPIO.1-Pad13)") (class "Default")
      (node (ref "U4") (pin "13") (pinfunction "GPIO.1_13") (pintype "passive"))
    )
    (net (code "86") (name "unconnected-(U4-GPIO.2-Pad12)") (class "Default")
      (node (ref "U4") (pin "12") (pinfunction "GPIO.2_12") (pintype "passive"))
    )
    (net (code "87") (name "unconnected-(U4-GPIO.3-Pad11)") (class "Default")
      (node (ref "U4") (pin "11") (pinfunction "GPIO.3_11") (pintype "passive"))
    )
    (net (code "88") (name "unconnected-(U4-NC-Pad10)") (class "Default")
      (node (ref "U4") (pin "10") (pinfunction "NC_10") (pintype "passive"))
    )
    (net (code "89") (name "unconnected-(U4-RI-Pad1)") (class "Default")
      (node (ref "U4") (pin "1") (pinfunction "RI_1") (pintype "passive"))
    )
    (net (code "90") (name "unconnected-(U4-RTS-Pad19)") (class "Default")
      (node (ref "U4") (pin "19") (pinfunction "RTS_19") (pintype "passive"))
    )
    (net (code "91") (name "unconnected-(U4-SUSPEND-Pad15)") (class "Default")
      (node (ref "U4") (pin "15") (pinfunction "SUSPEND_15") (pintype "passive"))
    )
    (net (code "92") (name "unconnected-(U4-VPP-Pad16)") (class "Default")
      (node (ref "U4") (pin "16") (pinfunction "VPP_16") (pintype "passive"))
    )
    (net (code "93") (name "unconnected-(U4-~{RST}-Pad9)") (class "Default")
      (node (ref "U4") (pin "9") (pinfunction "~{RST}_9") (pintype "passive"))
    )
    (net (code "94") (name "unconnected-(U4-~{SUSPEND}-Pad17)") (class "Default")
      (node (ref "U4") (pin "17") (pinfunction "~{SUSPEND}_17") (pintype "passive"))
    )
    (net (code "95") (name "unconnected-(U5-D3+-Pad8)") (class "Default")
      (node (ref "U5") (pin "8") (pinfunction "D3+_8") (pintype "passive"))
    )
    (net (code "96") (name "unconnected-(U5-D3--Pad7)") (class "Default")
      (node (ref "U5") (pin "7") (pinfunction "D3-_7") (pintype "passive"))
    )
    (net (code "97") (name "unconnected-(U5-NC-Pad16)") (class "Default")
      (node (ref "U5") (pin "16") (pinfunction "NC_16") (pintype "passive"))
    )
    (net (code "98") (name "unconnected-(U6-PA11[PA9]-Pad18)") (class "Default")
      (node (ref "U6") (pin "18") (pinfunction "PA11[PA9]_18") (pintype "passive"))
    )
    (net (code "99") (name "unconnected-(U6-PA12[PA10]-Pad19)") (class "Default")
      (node (ref "U6") (pin "19") (pinfunction "PA12[PA10]_19") (pintype "passive"))
    )
    (net (code "100") (name "unconnected-(U6-PB4-Pad24)") (class "Default")
      (node (ref "U6") (pin "24") (pinfunction "PB4_24") (pintype "passive"))
    )
    (net (code "101") (name "unconnected-(U6-PB8-Pad28)") (class "Default")
      (node (ref "U6") (pin "28") (pinfunction "PB8_28") (pintype "passive"))
    )
    (net (code "102") (name "unconnected-(U7-CHG#-Pad9)") (class "Default")
      (node (ref "U7") (pin "9") (pinfunction "CHG#_9") (pintype "passive"))
    )
    (net (code "103") (name "unconnected-(U7-PGOOD#-Pad7)") (class "Default")
      (node (ref "U7") (pin "7") (pinfunction "PGOOD#_7") (pintype "passive"))
    )
    (net (code "104") (name "unconnected-(U7-TMR-Pad14)") (class "Default")
      (node (ref "U7") (pin "14") (pinfunction "TMR_14") (pintype "passive+no_connect"))
    )
  )
)
